# ESP32_Schematic.net
KiCad netlist of a schematic drawn in Altium Designer
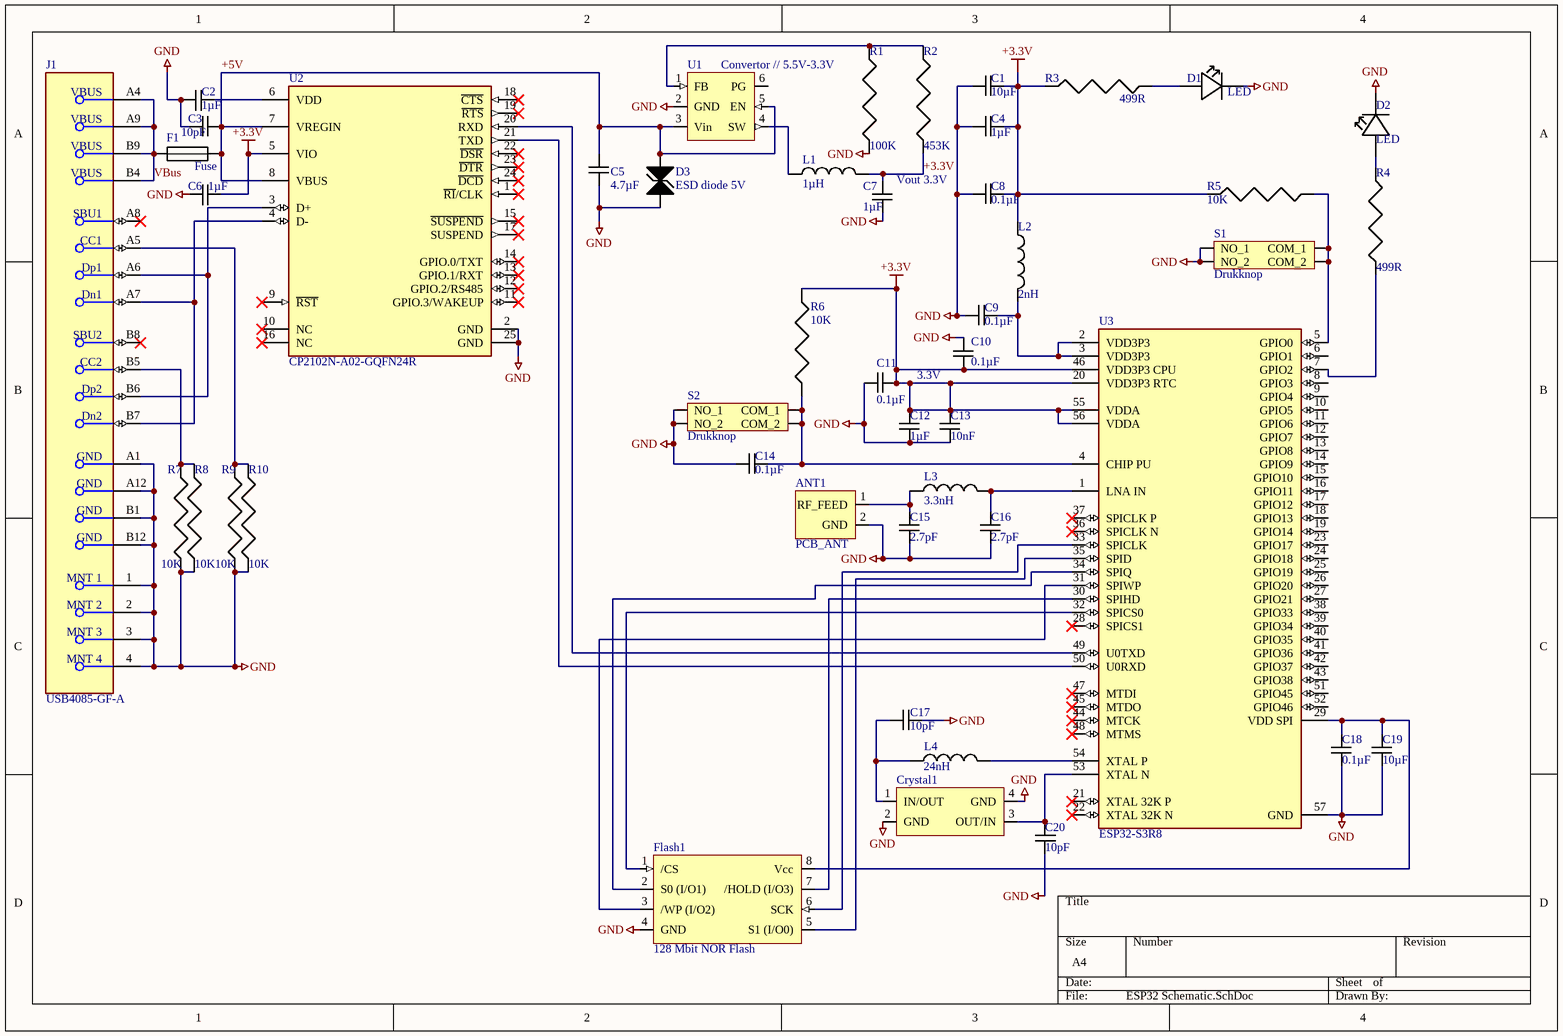
[diagram p0: ESP32 Schematic.SchDoc]

(export (version "E")
  (design (tool "Eeschema 10.0.6"))
  (components
    (comp (ref "ANT1")
      (value "PCB_ANT")
      (footprint "Antenne // RFANT5220110A0T")
      (libsource (lib "Schematic-Library") (part "Antenne // RFANT5220110A0T"))
    )
    (comp (ref "C1")
      (value "10µF")
      (footprint "CAP_General_0603")
      (description "Capacitor SMD 0603 ?pF")
      (libsource (lib "Schematic-Library") (part "CAP_General_0603"))
    )
    (comp (ref "C2")
      (value "1µF")
      (footprint "CAP_General_0603")
      (description "Capacitor SMD 0603 ?pF")
      (libsource (lib "Schematic-Library") (part "CAP_General_0603"))
    )
    (comp (ref "C3")
      (value "10pF")
      (footprint "CAP_General_0603")
      (description "Capacitor SMD 0603 ?pF")
      (libsource (lib "Schematic-Library") (part "CAP_General_0603"))
    )
    (comp (ref "C4")
      (value "1µF")
      (footprint "CAP_General_0603")
      (description "Capacitor SMD 0603 ?pF")
      (libsource (lib "Schematic-Library") (part "CAP_General_0603"))
    )
    (comp (ref "C5")
      (value "4.7µF")
      (footprint "CAP_General_0603")
      (description "Capacitor SMD 0603 ?pF")
      (libsource (lib "Schematic-Library") (part "CAP_General_0603"))
    )
    (comp (ref "C6")
      (value "1µF")
      (footprint "CAP_General_0603")
      (description "Capacitor SMD 0603 ?pF")
      (libsource (lib "Schematic-Library") (part "CAP_General_0603"))
    )
    (comp (ref "C7")
      (value "1µF")
      (footprint "CAP_General_0603")
      (description "Capacitor SMD 0603 ?pF")
      (libsource (lib "Schematic-Library") (part "CAP_General_0603"))
    )
    (comp (ref "C8")
      (value "0.1µF")
      (footprint "CAP_General_0603")
      (description "Capacitor SMD 0603 ?pF")
      (libsource (lib "Schematic-Library") (part "CAP_General_0603"))
    )
    (comp (ref "C9")
      (value "0.1µF")
      (footprint "CAP_General_0603")
      (description "Capacitor SMD 0603 ?pF")
      (libsource (lib "Schematic-Library") (part "CAP_General_0603"))
    )
    (comp (ref "C10")
      (value "0.1µF")
      (footprint "CAP_General_0603")
      (description "Capacitor SMD 0603 ?pF")
      (libsource (lib "Schematic-Library") (part "CAP_General_0603"))
    )
    (comp (ref "C11")
      (value "0.1µF")
      (footprint "CAP_General_0603")
      (description "Capacitor SMD 0603 ?pF")
      (libsource (lib "Schematic-Library") (part "CAP_General_0603"))
    )
    (comp (ref "C12")
      (value "1µF")
      (footprint "CAP_General_0603")
      (description "Capacitor SMD 0603 ?pF")
      (libsource (lib "Schematic-Library") (part "CAP_General_0603"))
    )
    (comp (ref "C13")
      (value "10nF")
      (footprint "CAP_General_0603")
      (description "Capacitor SMD 0603 ?pF")
      (libsource (lib "Schematic-Library") (part "CAP_General_0603"))
    )
    (comp (ref "C14")
      (value "0.1µF")
      (footprint "CAP_General_0603")
      (description "Capacitor SMD 0603 ?pF")
      (libsource (lib "Schematic-Library") (part "CAP_General_0603"))
    )
    (comp (ref "C15")
      (value "2.7pF")
      (footprint "CAP_General_0603")
      (description "Capacitor SMD 0603 ?pF")
      (libsource (lib "Schematic-Library") (part "CAP_General_0603"))
    )
    (comp (ref "C16")
      (value "2.7pF")
      (footprint "CAP_General_0603")
      (description "Capacitor SMD 0603 ?pF")
      (libsource (lib "Schematic-Library") (part "CAP_General_0603"))
    )
    (comp (ref "C17")
      (value "10pF")
      (footprint "CAP_General_0603")
      (description "Capacitor SMD 0603 ?pF")
      (libsource (lib "Schematic-Library") (part "CAP_General_0603"))
    )
    (comp (ref "C18")
      (value "0.1µF")
      (footprint "CAP_General_0603")
      (description "Capacitor SMD 0603 ?pF")
      (libsource (lib "Schematic-Library") (part "CAP_General_0603"))
    )
    (comp (ref "C19")
      (value "10µF")
      (footprint "CAP_General_0603")
      (description "Capacitor SMD 0603 ?pF")
      (libsource (lib "Schematic-Library") (part "CAP_General_0603"))
    )
    (comp (ref "C20")
      (value "10pF")
      (footprint "CAP_General_0603")
      (description "Capacitor SMD 0603 ?pF")
      (libsource (lib "Schematic-Library") (part "CAP_General_0603"))
    )
    (comp (ref "Crystal1")
      (value "Crystal")
      (footprint "Crystal // ECS­400­8­47B2­CKM­TR")
      (libsource (lib "Schematic-Library") (part "Crystal // ECS­400­8­47B2­CKM­TR"))
    )
    (comp (ref "D1")
      (value "LED")
      (footprint "LED // KRDELPS1.22-UIVG-46-H3Q4-XX")
      (libsource (lib "Schematic-Library") (part "LED // KRDELPS1.22-UIVG-46-H3Q4-XX"))
    )
    (comp (ref "D2")
      (value "LED")
      (footprint "LED // KRDELPS1.22-UIVG-46-H3Q4-XX")
      (libsource (lib "Schematic-Library") (part "LED // KRDELPS1.22-UIVG-46-H3Q4-XX"))
    )
    (comp (ref "D3")
      (value "ESD diode 5V")
      (footprint "ESD diode 5V // SMF5.0A")
      (libsource (lib "Schematic-Library") (part "ESD diode 5V // SMF5.0A"))
    )
    (comp (ref "F1")
      (value "Fuse")
      (footprint "Fuse // 0603L050SLYR")
      (libsource (lib "Schematic-Library") (part "Fuse // 0603L050SLYR"))
    )
    (comp (ref "Flash1")
      (value "128 Mbit NOR Flash")
      (footprint "128 Mbit NOR Flash // AT25QF128A-MHB-T")
      (libsource (lib "Schematic-Library") (part "128 Mbit NOR Flash // AT25QF128A-MHB-T"))
    )
    (comp (ref "J1")
      (value "USB4085-GF-A")
      (footprint "USB-C connector // USB4085-GF-A")
      (description "CONN RCPT USB2.0 TYPE C 24POS RA")
      (libsource (lib "Schematic-Library") (part "USB-C connector // USB4085-GF-A"))
    )
    (comp (ref "L1")
      (value "1µH")
      (footprint "Inductor 1µH // MLP2520H1R0MT0S1")
      (libsource (lib "Schematic-Library") (part "Inductor 1µH // MLP2520H1R0MT0S1"))
    )
    (comp (ref "L2")
      (value "2nH")
      (footprint "Inductor 2nH // MLG1005S2N0BTD25")
      (libsource (lib "Schematic-Library") (part "Inductor 2nH // MLG1005S2N0BTD25"))
    )
    (comp (ref "L3")
      (value "3.3nH")
      (footprint "Inductor 3.3nH // AIMC-0805-3N3")
      (libsource (lib "Schematic-Library") (part "Inductor 3.3nH // AIMC-0805-3N3"))
    )
    (comp (ref "L4")
      (value "24nH")
      (footprint "Inductor 24 nH // 36501J24NJTDG")
      (libsource (lib "Schematic-Library") (part "Inductor 24 nH // 36501J24NJTDG"))
    )
    (comp (ref "R1")
      (value "100K")
      (footprint "RES_100K_0603")
      (description "Resistor SMD 0603 100K")
      (libsource (lib "Schematic-Library") (part "RES_100K_0603"))
    )
    (comp (ref "R2")
      (value "453K")
      (footprint "RES_453K_0603")
      (description "Resistor SMD 0603 453K")
      (libsource (lib "Schematic-Library") (part "RES_453K_0603"))
    )
    (comp (ref "R3")
      (value "499R")
      (footprint "RES_499R_0603")
      (description "Resistor SMD 0603 499R")
      (libsource (lib "Schematic-Library") (part "RES_499R_0603"))
    )
    (comp (ref "R4")
      (value "499R")
      (footprint "RES_499R_0603")
      (description "Resistor SMD 0603 499R")
      (libsource (lib "Schematic-Library") (part "RES_499R_0603"))
    )
    (comp (ref "R5")
      (value "10K")
      (footprint "RES_10K_0603_1")
      (description "Resistor SMD 0603 10K")
      (libsource (lib "Schematic-Library") (part "RES_10K_0603_1"))
    )
    (comp (ref "R6")
      (value "10K")
      (footprint "RES_10K_0603_1")
      (description "Resistor SMD 0603 10K")
      (libsource (lib "Schematic-Library") (part "RES_10K_0603_1"))
    )
    (comp (ref "R7")
      (value "10K")
      (footprint "RES_10K_0603_1")
      (description "Resistor SMD 0603 10K")
      (libsource (lib "Schematic-Library") (part "RES_10K_0603_1"))
    )
    (comp (ref "R8")
      (value "10K")
      (footprint "RES_10K_0603_1")
      (description "Resistor SMD 0603 10K")
      (libsource (lib "Schematic-Library") (part "RES_10K_0603_1"))
    )
    (comp (ref "R9")
      (value "10K")
      (footprint "RES_10K_0603_1")
      (description "Resistor SMD 0603 10K")
      (libsource (lib "Schematic-Library") (part "RES_10K_0603_1"))
    )
    (comp (ref "R10")
      (value "10K")
      (footprint "RES_10K_0603_1")
      (description "Resistor SMD 0603 10K")
      (libsource (lib "Schematic-Library") (part "RES_10K_0603_1"))
    )
    (comp (ref "S1")
      (value "Drukknop")
      (footprint "Tactile Switches // FSM4JSMAATR")
      (libsource (lib "Schematic-Library") (part "Tactile Switches // FSM4JSMAATR"))
    )
    (comp (ref "S2")
      (value "Drukknop")
      (footprint "Tactile Switches // FSM4JSMAATR")
      (libsource (lib "Schematic-Library") (part "Tactile Switches // FSM4JSMAATR"))
    )
    (comp (ref "U1")
      (value "Convertor // 5.5V-3.3V")
      (footprint "CONVERTOR // TLV62569APDRLR")
      (libsource (lib "Schematic-Library") (part "Convertor // TLV62569APDRLR"))
    )
    (comp (ref "U2")
      (value "CP2102N-A02-GQFN24R")
      (footprint "USB Bridge // CP2102N-A02-GQFN24R")
      (description "IC USB TO UART BRIDGE QFN24")
      (libsource (lib "Schematic-Library") (part "USB Bridge // CP2102N-A02-GQFN24R"))
    )
    (comp (ref "U3")
      (value "ESP32-S3R8")
      (footprint "FP-ESP32-S3R8")
      (description "ESP32-S3R8 RF System on a Chip - SoC SMD IC, Dual-Core MCU, Wi-Fi 2.4G BLE 5.0 Combo")
      (libsource (lib "Schematic-Library") (part "ESP32-S3"))
    )
  )
  (nets
    (net (code "1") (name "+3.3V") (class "Default")
      (node (ref "C1") (pin "2") (pintype "passive"))
      (node (ref "C10") (pin "1") (pintype "passive"))
      (node (ref "C11") (pin "2") (pintype "passive"))
      (node (ref "C12") (pin "2") (pintype "passive"))
      (node (ref "C13") (pin "2") (pintype "passive"))
      (node (ref "C4") (pin "2") (pintype "passive"))
      (node (ref "C6") (pin "1") (pintype "passive"))
      (node (ref "C7") (pin "2") (pintype "passive"))
      (node (ref "C8") (pin "2") (pintype "passive"))
      (node (ref "L1") (pin "2") (pinfunction "4_2") (pintype "passive"))
      (node (ref "L2") (pin "1") (pinfunction "3_1") (pintype "passive"))
      (node (ref "R2") (pin "2") (pintype "passive"))
      (node (ref "R3") (pin "1") (pintype "passive"))
      (node (ref "R5") (pin "1") (pintype "passive"))
      (node (ref "R6") (pin "2") (pintype "passive"))
      (node (ref "U2") (pin "5") (pinfunction "VIO_5") (pintype "power_in"))
      (node (ref "U3") (pin "20") (pinfunction "VDD3P3_RTC_20") (pintype "power_in"))
      (node (ref "U3") (pin "46") (pinfunction "VDD3P3_CPU_46") (pintype "power_in"))
      (node (ref "U3") (pin "55") (pinfunction "VDDA_55") (pintype "power_in"))
      (node (ref "U3") (pin "56") (pinfunction "VDDA_56") (pintype "power_in"))
    )
    (net (code "2") (name "/+5V") (class "Default")
      (node (ref "C3") (pin "2") (pintype "passive"))
      (node (ref "C5") (pin "2") (pintype "passive"))
      (node (ref "D3") (pin "1") (pintype "passive"))
      (node (ref "F1") (pin "2") (pinfunction "14_2") (pintype "passive"))
      (node (ref "U1") (pin "3") (pinfunction "Vin_3") (pintype "power_in"))
      (node (ref "U1") (pin "5") (pinfunction "EN_5") (pintype "input"))
      (node (ref "U2") (pin "7") (pinfunction "VREGIN_7") (pintype "power_in"))
      (node (ref "U2") (pin "8") (pinfunction "VBUS_8") (pintype "power_in"))
    )
    (net (code "3") (name "/VBus") (class "Default")
      (node (ref "F1") (pin "1") (pinfunction "13_1") (pintype "passive"))
      (node (ref "J1") (pin "A4") (pinfunction "VBUS_A4") (pintype "power_in"))
      (node (ref "J1") (pin "A9") (pinfunction "VBUS_A9") (pintype "power_in"))
      (node (ref "J1") (pin "B4") (pinfunction "VBUS_B4") (pintype "power_in"))
      (node (ref "J1") (pin "B9") (pinfunction "VBUS_B9") (pintype "power_in"))
    )
    (net (code "4") (name "GND") (class "Default")
      (node (ref "ANT1") (pin "2") (pinfunction "GND_2") (pintype "power_in"))
      (node (ref "C1") (pin "1") (pintype "passive"))
      (node (ref "C10") (pin "2") (pintype "passive"))
      (node (ref "C11") (pin "1") (pintype "passive"))
      (node (ref "C12") (pin "1") (pintype "passive"))
      (node (ref "C13") (pin "1") (pintype "passive"))
      (node (ref "C14") (pin "1") (pintype "passive"))
      (node (ref "C15") (pin "1") (pintype "passive"))
      (node (ref "C16") (pin "1") (pintype "passive"))
      (node (ref "C17") (pin "2") (pintype "passive"))
      (node (ref "C18") (pin "1") (pintype "passive"))
      (node (ref "C19") (pin "1") (pintype "passive"))
      (node (ref "C2") (pin "2") (pintype "passive"))
      (node (ref "C20") (pin "2") (pintype "passive"))
      (node (ref "C3") (pin "1") (pintype "passive"))
      (node (ref "C4") (pin "1") (pintype "passive"))
      (node (ref "C5") (pin "1") (pintype "passive"))
      (node (ref "C6") (pin "2") (pintype "passive"))
      (node (ref "C7") (pin "1") (pintype "passive"))
      (node (ref "C8") (pin "1") (pintype "passive"))
      (node (ref "C9") (pin "1") (pintype "passive"))
      (node (ref "Crystal1") (pin "2") (pinfunction "GND_2") (pintype "power_in"))
      (node (ref "Crystal1") (pin "4") (pinfunction "GND_4") (pintype "power_in"))
      (node (ref "D1") (pin "2") (pinfunction "16_2") (pintype "passive"))
      (node (ref "D2") (pin "2") (pinfunction "16_2") (pintype "passive"))
      (node (ref "D3") (pin "2") (pinfunction "2_2") (pintype "passive"))
      (node (ref "Flash1") (pin "4") (pinfunction "GND_4") (pintype "power_in"))
      (node (ref "J1") (pin "1") (pinfunction "MNT_1_1") (pintype "passive"))
      (node (ref "J1") (pin "2") (pinfunction "MNT_2_2") (pintype "passive"))
      (node (ref "J1") (pin "3") (pinfunction "MNT_3_3") (pintype "passive"))
      (node (ref "J1") (pin "4") (pinfunction "MNT_4_4") (pintype "passive"))
      (node (ref "J1") (pin "A1") (pinfunction "GND_A1") (pintype "power_in"))
      (node (ref "J1") (pin "A12") (pinfunction "GND_A12") (pintype "power_in"))
      (node (ref "J1") (pin "B1") (pinfunction "GND_B1") (pintype "power_in"))
      (node (ref "J1") (pin "B12") (pinfunction "GND_B12") (pintype "power_in"))
      (node (ref "R1") (pin "1") (pintype "passive"))
      (node (ref "R10") (pin "1") (pintype "passive"))
      (node (ref "R7") (pin "1") (pintype "passive"))
      (node (ref "R8") (pin "1") (pintype "passive"))
      (node (ref "R9") (pin "1") (pintype "passive"))
      (node (ref "S1") (pin "3") (pinfunction "NO_1_3") (pintype "passive"))
      (node (ref "S1") (pin "4") (pinfunction "NO_2_4") (pintype "passive"))
      (node (ref "S2") (pin "3") (pinfunction "NO_1_3") (pintype "passive"))
      (node (ref "S2") (pin "4") (pinfunction "NO_2_4") (pintype "passive"))
      (node (ref "U1") (pin "2") (pinfunction "GND_2") (pintype "power_in"))
      (node (ref "U2") (pin "2") (pinfunction "GND_2") (pintype "power_in"))
      (node (ref "U2") (pin "25") (pinfunction "GND_25") (pintype "power_in"))
      (node (ref "U3") (pin "57") (pinfunction "GND_57") (pintype "power_in"))
    )
    (net (code "5") (name "Net-(ANT1-RF_FEED)") (class "Default")
      (node (ref "ANT1") (pin "1") (pinfunction "RF_FEED_1") (pintype "passive"))
      (node (ref "C15") (pin "2") (pintype "passive"))
      (node (ref "L3") (pin "1") (pinfunction "3_1") (pintype "passive"))
    )
    (net (code "6") (name "Net-(Crystal1-IN{slash}OUT)") (class "Default")
      (node (ref "C17") (pin "1") (pintype "passive"))
      (node (ref "Crystal1") (pin "1") (pinfunction "IN/OUT_1") (pintype "bidirectional"))
      (node (ref "L4") (pin "1") (pinfunction "3_1") (pintype "passive"))
    )
    (net (code "7") (name "Net-(Crystal1-OUT{slash}IN)") (class "Default")
      (node (ref "C20") (pin "1") (pintype "passive"))
      (node (ref "Crystal1") (pin "3") (pinfunction "OUT/IN_3") (pintype "bidirectional"))
      (node (ref "U3") (pin "53") (pinfunction "XTAL_N_53") (pintype "passive"))
    )
    (net (code "8") (name "Net-(D1-15)") (class "Default")
      (node (ref "D1") (pin "1") (pinfunction "15_1") (pintype "passive"))
      (node (ref "R3") (pin "2") (pintype "passive"))
    )
    (net (code "9") (name "Net-(D2-15)") (class "Default")
      (node (ref "D2") (pin "1") (pinfunction "15_1") (pintype "passive"))
      (node (ref "R4") (pin "2") (pintype "passive"))
    )
    (net (code "10") (name "Net-(Flash1-S0_(I{slash}O1))") (class "Default")
      (node (ref "Flash1") (pin "2") (pinfunction "S0_(I/O1)_2") (pintype "bidirectional"))
      (node (ref "U3") (pin "34") (pinfunction "SPIQ_34") (pintype "bidirectional"))
    )
    (net (code "11") (name "Net-(Flash1-S1_(I{slash}O0))") (class "Default")
      (node (ref "Flash1") (pin "5") (pinfunction "S1_(I/O0)_5") (pintype "bidirectional"))
      (node (ref "U3") (pin "35") (pinfunction "SPID_35") (pintype "bidirectional"))
    )
    (net (code "12") (name "Net-(Flash1-SCK)") (class "Default")
      (node (ref "Flash1") (pin "6") (pinfunction "SCK_6") (pintype "input"))
      (node (ref "U3") (pin "33") (pinfunction "SPICLK_33") (pintype "bidirectional"))
    )
    (net (code "13") (name "Net-(Flash1-Vcc)") (class "Default")
      (node (ref "C18") (pin "2") (pintype "passive"))
      (node (ref "C19") (pin "2") (pintype "passive"))
      (node (ref "Flash1") (pin "8") (pinfunction "Vcc_8") (pintype "power_in"))
      (node (ref "U3") (pin "29") (pinfunction "VDD_SPI_29") (pintype "power_in"))
    )
    (net (code "14") (name "Net-(Flash1-{slash}CS)") (class "Default")
      (node (ref "Flash1") (pin "1") (pinfunction "/CS_1") (pintype "input"))
      (node (ref "U3") (pin "32") (pinfunction "SPICS0_32") (pintype "bidirectional"))
    )
    (net (code "15") (name "Net-(Flash1-{slash}HOLD_(I{slash}O3))") (class "Default")
      (node (ref "Flash1") (pin "7") (pinfunction "/HOLD_(I/O3)_7") (pintype "bidirectional"))
      (node (ref "U3") (pin "30") (pinfunction "SPIHD_30") (pintype "bidirectional"))
    )
    (net (code "16") (name "Net-(Flash1-{slash}WP_(I{slash}O2))") (class "Default")
      (node (ref "Flash1") (pin "3") (pinfunction "/WP_(I/O2)_3") (pintype "bidirectional"))
      (node (ref "U3") (pin "31") (pinfunction "SPIWP_31") (pintype "bidirectional"))
    )
    (net (code "17") (name "Net-(J1-CC1)") (class "Default")
      (node (ref "J1") (pin "A5") (pinfunction "CC1_A5") (pintype "bidirectional"))
      (node (ref "R10") (pin "2") (pintype "passive"))
      (node (ref "R9") (pin "2") (pintype "passive"))
    )
    (net (code "18") (name "Net-(J1-CC2)") (class "Default")
      (node (ref "J1") (pin "B5") (pinfunction "CC2_B5") (pintype "bidirectional"))
      (node (ref "R7") (pin "2") (pintype "passive"))
      (node (ref "R8") (pin "2") (pintype "passive"))
    )
    (net (code "19") (name "Net-(J1-Dn1)") (class "Default")
      (node (ref "J1") (pin "A7") (pinfunction "Dn1_A7") (pintype "bidirectional"))
      (node (ref "J1") (pin "B7") (pinfunction "Dn2_B7") (pintype "bidirectional"))
      (node (ref "U2") (pin "4") (pinfunction "D-_4") (pintype "bidirectional"))
    )
    (net (code "20") (name "Net-(J1-Dp1)") (class "Default")
      (node (ref "J1") (pin "A6") (pinfunction "Dp1_A6") (pintype "bidirectional"))
      (node (ref "J1") (pin "B6") (pinfunction "Dp2_B6") (pintype "bidirectional"))
      (node (ref "U2") (pin "3") (pinfunction "D+_3") (pintype "bidirectional"))
    )
    (net (code "21") (name "Net-(L1-3)") (class "Default")
      (node (ref "L1") (pin "1") (pinfunction "3_1") (pintype "passive"))
      (node (ref "U1") (pin "4") (pinfunction "SW_4") (pintype "output"))
    )
    (net (code "22") (name "Net-(L2-4)") (class "Default")
      (node (ref "C9") (pin "2") (pintype "passive"))
      (node (ref "L2") (pin "2") (pinfunction "4_2") (pintype "passive"))
      (node (ref "U3") (pin "2") (pinfunction "VDD3P3_2") (pintype "power_in"))
      (node (ref "U3") (pin "3") (pinfunction "VDD3P3_3") (pintype "power_in"))
    )
    (net (code "23") (name "Net-(L3-4)") (class "Default")
      (node (ref "C16") (pin "2") (pintype "passive"))
      (node (ref "L3") (pin "2") (pinfunction "4_2") (pintype "passive"))
      (node (ref "U3") (pin "1") (pinfunction "LNA_IN_1") (pintype "passive"))
    )
    (net (code "24") (name "Net-(L4-4)") (class "Default")
      (node (ref "L4") (pin "2") (pinfunction "4_2") (pintype "passive"))
      (node (ref "U3") (pin "54") (pinfunction "XTAL_P_54") (pintype "passive"))
    )
    (net (code "25") (name "Net-(S1-COM_1)") (class "Default")
      (node (ref "R5") (pin "2") (pintype "passive"))
      (node (ref "S1") (pin "1") (pinfunction "COM_1_1") (pintype "passive"))
      (node (ref "S1") (pin "2") (pinfunction "COM_2_2") (pintype "passive"))
      (node (ref "U3") (pin "5") (pinfunction "GPIO0_5") (pintype "bidirectional"))
    )
    (net (code "26") (name "Net-(S2-COM_1)") (class "Default")
      (node (ref "C14") (pin "2") (pintype "passive"))
      (node (ref "R6") (pin "1") (pintype "passive"))
      (node (ref "S2") (pin "1") (pinfunction "COM_1_1") (pintype "passive"))
      (node (ref "S2") (pin "2") (pinfunction "COM_2_2") (pintype "passive"))
      (node (ref "U3") (pin "4") (pinfunction "CHIP_PU_4") (pintype "passive"))
    )
    (net (code "27") (name "Net-(U1-FB)") (class "Default")
      (node (ref "R1") (pin "2") (pintype "passive"))
      (node (ref "R2") (pin "1") (pintype "passive"))
      (node (ref "U1") (pin "1") (pinfunction "FB_1") (pintype "input"))
    )
    (net (code "28") (name "Net-(U2-RXD)") (class "Default")
      (node (ref "U2") (pin "20") (pinfunction "RXD_20") (pintype "input"))
      (node (ref "U3") (pin "49") (pinfunction "U0TXD_49") (pintype "bidirectional"))
    )
    (net (code "29") (name "Net-(U2-TXD)") (class "Default")
      (node (ref "U2") (pin "21") (pinfunction "TXD_21") (pintype "output"))
      (node (ref "U3") (pin "50") (pinfunction "U0RXD_50") (pintype "bidirectional"))
    )
    (net (code "30") (name "Net-(U2-VDD)") (class "Default")
      (node (ref "C2") (pin "1") (pintype "passive"))
      (node (ref "U2") (pin "6") (pinfunction "VDD_6") (pintype "power_in"))
    )
    (net (code "31") (name "Net-(U3-GPIO2)") (class "Default")
      (node (ref "R4") (pin "1") (pintype "passive"))
      (node (ref "U3") (pin "7") (pinfunction "GPIO2_7") (pintype "bidirectional"))
    )
    (net (code "32") (name "unconnected-(J1-SBU1-PadA8)") (class "Default")
      (node (ref "J1") (pin "A8") (pinfunction "SBU1_A8") (pintype "bidirectional+no_connect"))
    )
    (net (code "33") (name "unconnected-(J1-SBU2-PadB8)") (class "Default")
      (node (ref "J1") (pin "B8") (pinfunction "SBU2_B8") (pintype "bidirectional+no_connect"))
    )
    (net (code "34") (name "unconnected-(U1-PG-Pad6)") (class "Default")
      (node (ref "U1") (pin "6") (pinfunction "PG_6") (pintype "open_collector"))
    )
    (net (code "35") (name "unconnected-(U2-GPIO.0{slash}TXT-Pad14)") (class "Default")
      (node (ref "U2") (pin "14") (pinfunction "GPIO.0/TXT_14") (pintype "bidirectional+no_connect"))
    )
    (net (code "36") (name "unconnected-(U2-GPIO.1{slash}RXT-Pad13)") (class "Default")
      (node (ref "U2") (pin "13") (pinfunction "GPIO.1/RXT_13") (pintype "bidirectional+no_connect"))
    )
    (net (code "37") (name "unconnected-(U2-GPIO.2{slash}RS485-Pad12)") (class "Default")
      (node (ref "U2") (pin "12") (pinfunction "GPIO.2/RS485_12") (pintype "bidirectional+no_connect"))
    )
    (net (code "38") (name "unconnected-(U2-GPIO.3{slash}WAKEUP-Pad11)") (class "Default")
      (node (ref "U2") (pin "11") (pinfunction "GPIO.3/WAKEUP_11") (pintype "bidirectional+no_connect"))
    )
    (net (code "39") (name "unconnected-(U2-NC-Pad10)") (class "Default")
      (node (ref "U2") (pin "10") (pinfunction "NC_10") (pintype "passive+no_connect"))
    )
    (net (code "40") (name "unconnected-(U2-NC-Pad16)") (class "Default")
      (node (ref "U2") (pin "16") (pinfunction "NC_16") (pintype "passive+no_connect"))
    )
    (net (code "41") (name "unconnected-(U2-SUSPEND-Pad17)") (class "Default")
      (node (ref "U2") (pin "17") (pinfunction "SUSPEND_17") (pintype "output+no_connect"))
    )
    (net (code "42") (name "unconnected-(U2-~{CTS}-Pad18)") (class "Default")
      (node (ref "U2") (pin "18") (pinfunction "~{CTS}_18") (pintype "input+no_connect"))
    )
    (net (code "43") (name "unconnected-(U2-~{DCD}-Pad24)") (class "Default")
      (node (ref "U2") (pin "24") (pinfunction "~{DCD}_24") (pintype "input+no_connect"))
    )
    (net (code "44") (name "unconnected-(U2-~{DSR}-Pad22)") (class "Default")
      (node (ref "U2") (pin "22") (pinfunction "~{DSR}_22") (pintype "input+no_connect"))
    )
    (net (code "45") (name "unconnected-(U2-~{DTR}-Pad23)") (class "Default")
      (node (ref "U2") (pin "23") (pinfunction "~{DTR}_23") (pintype "output+no_connect"))
    )
    (net (code "46") (name "unconnected-(U2-~{RI}{slash}CLK-Pad1)") (class "Default")
      (node (ref "U2") (pin "1") (pinfunction "~{RI}/CLK_1") (pintype "input+no_connect"))
    )
    (net (code "47") (name "unconnected-(U2-~{RST}-Pad9)") (class "Default")
      (node (ref "U2") (pin "9") (pinfunction "~{RST}_9") (pintype "input+no_connect"))
    )
    (net (code "48") (name "unconnected-(U2-~{RTS}-Pad19)") (class "Default")
      (node (ref "U2") (pin "19") (pinfunction "~{RTS}_19") (pintype "output+no_connect"))
    )
    (net (code "49") (name "unconnected-(U2-~{SUSPEND}-Pad15)") (class "Default")
      (node (ref "U2") (pin "15") (pinfunction "~{SUSPEND}_15") (pintype "output+no_connect"))
    )
    (net (code "50") (name "unconnected-(U3-GPIO1-Pad6)") (class "Default")
      (node (ref "U3") (pin "6") (pinfunction "GPIO1_6") (pintype "bidirectional"))
    )
    (net (code "51") (name "unconnected-(U3-GPIO3-Pad8)") (class "Default")
      (node (ref "U3") (pin "8") (pinfunction "GPIO3_8") (pintype "bidirectional"))
    )
    (net (code "52") (name "unconnected-(U3-GPIO4-Pad9)") (class "Default")
      (node (ref "U3") (pin "9") (pinfunction "GPIO4_9") (pintype "bidirectional"))
    )
    (net (code "53") (name "unconnected-(U3-GPIO5-Pad10)") (class "Default")
      (node (ref "U3") (pin "10") (pinfunction "GPIO5_10") (pintype "bidirectional"))
    )
    (net (code "54") (name "unconnected-(U3-GPIO6-Pad11)") (class "Default")
      (node (ref "U3") (pin "11") (pinfunction "GPIO6_11") (pintype "bidirectional"))
    )
    (net (code "55") (name "unconnected-(U3-GPIO7-Pad12)") (class "Default")
      (node (ref "U3") (pin "12") (pinfunction "GPIO7_12") (pintype "bidirectional"))
    )
    (net (code "56") (name "unconnected-(U3-GPIO8-Pad13)") (class "Default")
      (node (ref "U3") (pin "13") (pinfunction "GPIO8_13") (pintype "bidirectional"))
    )
    (net (code "57") (name "unconnected-(U3-GPIO9-Pad14)") (class "Default")
      (node (ref "U3") (pin "14") (pinfunction "GPIO9_14") (pintype "bidirectional"))
    )
    (net (code "58") (name "unconnected-(U3-GPIO10-Pad15)") (class "Default")
      (node (ref "U3") (pin "15") (pinfunction "GPIO10_15") (pintype "bidirectional"))
    )
    (net (code "59") (name "unconnected-(U3-GPIO11-Pad16)") (class "Default")
      (node (ref "U3") (pin "16") (pinfunction "GPIO11_16") (pintype "bidirectional"))
    )
    (net (code "60") (name "unconnected-(U3-GPIO12-Pad17)") (class "Default")
      (node (ref "U3") (pin "17") (pinfunction "GPIO12_17") (pintype "bidirectional"))
    )
    (net (code "61") (name "unconnected-(U3-GPIO13-Pad18)") (class "Default")
      (node (ref "U3") (pin "18") (pinfunction "GPIO13_18") (pintype "bidirectional"))
    )
    (net (code "62") (name "unconnected-(U3-GPIO14-Pad19)") (class "Default")
      (node (ref "U3") (pin "19") (pinfunction "GPIO14_19") (pintype "bidirectional"))
    )
    (net (code "63") (name "unconnected-(U3-GPIO17-Pad23)") (class "Default")
      (node (ref "U3") (pin "23") (pinfunction "GPIO17_23") (pintype "bidirectional"))
    )
    (net (code "64") (name "unconnected-(U3-GPIO18-Pad24)") (class "Default")
      (node (ref "U3") (pin "24") (pinfunction "GPIO18_24") (pintype "bidirectional"))
    )
    (net (code "65") (name "unconnected-(U3-GPIO19-Pad25)") (class "Default")
      (node (ref "U3") (pin "25") (pinfunction "GPIO19_25") (pintype "bidirectional"))
    )
    (net (code "66") (name "unconnected-(U3-GPIO20-Pad26)") (class "Default")
      (node (ref "U3") (pin "26") (pinfunction "GPIO20_26") (pintype "bidirectional"))
    )
    (net (code "67") (name "unconnected-(U3-GPIO21-Pad27)") (class "Default")
      (node (ref "U3") (pin "27") (pinfunction "GPIO21_27") (pintype "bidirectional"))
    )
    (net (code "68") (name "unconnected-(U3-GPIO33-Pad38)") (class "Default")
      (node (ref "U3") (pin "38") (pinfunction "GPIO33_38") (pintype "bidirectional"))
    )
    (net (code "69") (name "unconnected-(U3-GPIO34-Pad39)") (class "Default")
      (node (ref "U3") (pin "39") (pinfunction "GPIO34_39") (pintype "bidirectional"))
    )
    (net (code "70") (name "unconnected-(U3-GPIO35-Pad40)") (class "Default")
      (node (ref "U3") (pin "40") (pinfunction "GPIO35_40") (pintype "bidirectional"))
    )
    (net (code "71") (name "unconnected-(U3-GPIO36-Pad41)") (class "Default")
      (node (ref "U3") (pin "41") (pinfunction "GPIO36_41") (pintype "bidirectional"))
    )
    (net (code "72") (name "unconnected-(U3-GPIO37-Pad42)") (class "Default")
      (node (ref "U3") (pin "42") (pinfunction "GPIO37_42") (pintype "bidirectional"))
    )
    (net (code "73") (name "unconnected-(U3-GPIO38-Pad43)") (class "Default")
      (node (ref "U3") (pin "43") (pinfunction "GPIO38_43") (pintype "bidirectional"))
    )
    (net (code "74") (name "unconnected-(U3-GPIO45-Pad51)") (class "Default")
      (node (ref "U3") (pin "51") (pinfunction "GPIO45_51") (pintype "bidirectional"))
    )
    (net (code "75") (name "unconnected-(U3-GPIO46-Pad52)") (class "Default")
      (node (ref "U3") (pin "52") (pinfunction "GPIO46_52") (pintype "bidirectional"))
    )
    (net (code "76") (name "unconnected-(U3-MTCK-Pad44)") (class "Default")
      (node (ref "U3") (pin "44") (pinfunction "MTCK_44") (pintype "bidirectional+no_connect"))
    )
    (net (code "77") (name "unconnected-(U3-MTDI-Pad47)") (class "Default")
      (node (ref "U3") (pin "47") (pinfunction "MTDI_47") (pintype "bidirectional+no_connect"))
    )
    (net (code "78") (name "unconnected-(U3-MTDO-Pad45)") (class "Default")
      (node (ref "U3") (pin "45") (pinfunction "MTDO_45") (pintype "bidirectional+no_connect"))
    )
    (net (code "79") (name "unconnected-(U3-MTMS-Pad48)") (class "Default")
      (node (ref "U3") (pin "48") (pinfunction "MTMS_48") (pintype "bidirectional+no_connect"))
    )
    (net (code "80") (name "unconnected-(U3-SPICLK_N-Pad36)") (class "Default")
      (node (ref "U3") (pin "36") (pinfunction "SPICLK_N_36") (pintype "bidirectional+no_connect"))
    )
    (net (code "81") (name "unconnected-(U3-SPICLK_P-Pad37)") (class "Default")
      (node (ref "U3") (pin "37") (pinfunction "SPICLK_P_37") (pintype "bidirectional+no_connect"))
    )
    (net (code "82") (name "unconnected-(U3-SPICS1-Pad28)") (class "Default")
      (node (ref "U3") (pin "28") (pinfunction "SPICS1_28") (pintype "bidirectional+no_connect"))
    )
    (net (code "83") (name "unconnected-(U3-XTAL_32K_N-Pad22)") (class "Default")
      (node (ref "U3") (pin "22") (pinfunction "XTAL_32K_N_22") (pintype "bidirectional+no_connect"))
    )
    (net (code "84") (name "unconnected-(U3-XTAL_32K_P-Pad21)") (class "Default")
      (node (ref "U3") (pin "21") (pinfunction "XTAL_32K_P_21") (pintype "bidirectional+no_connect"))
    )
  )
)
